# WeatherBoard_v2_0.net
KiCad netlist of a schematic drawn in EAGLE
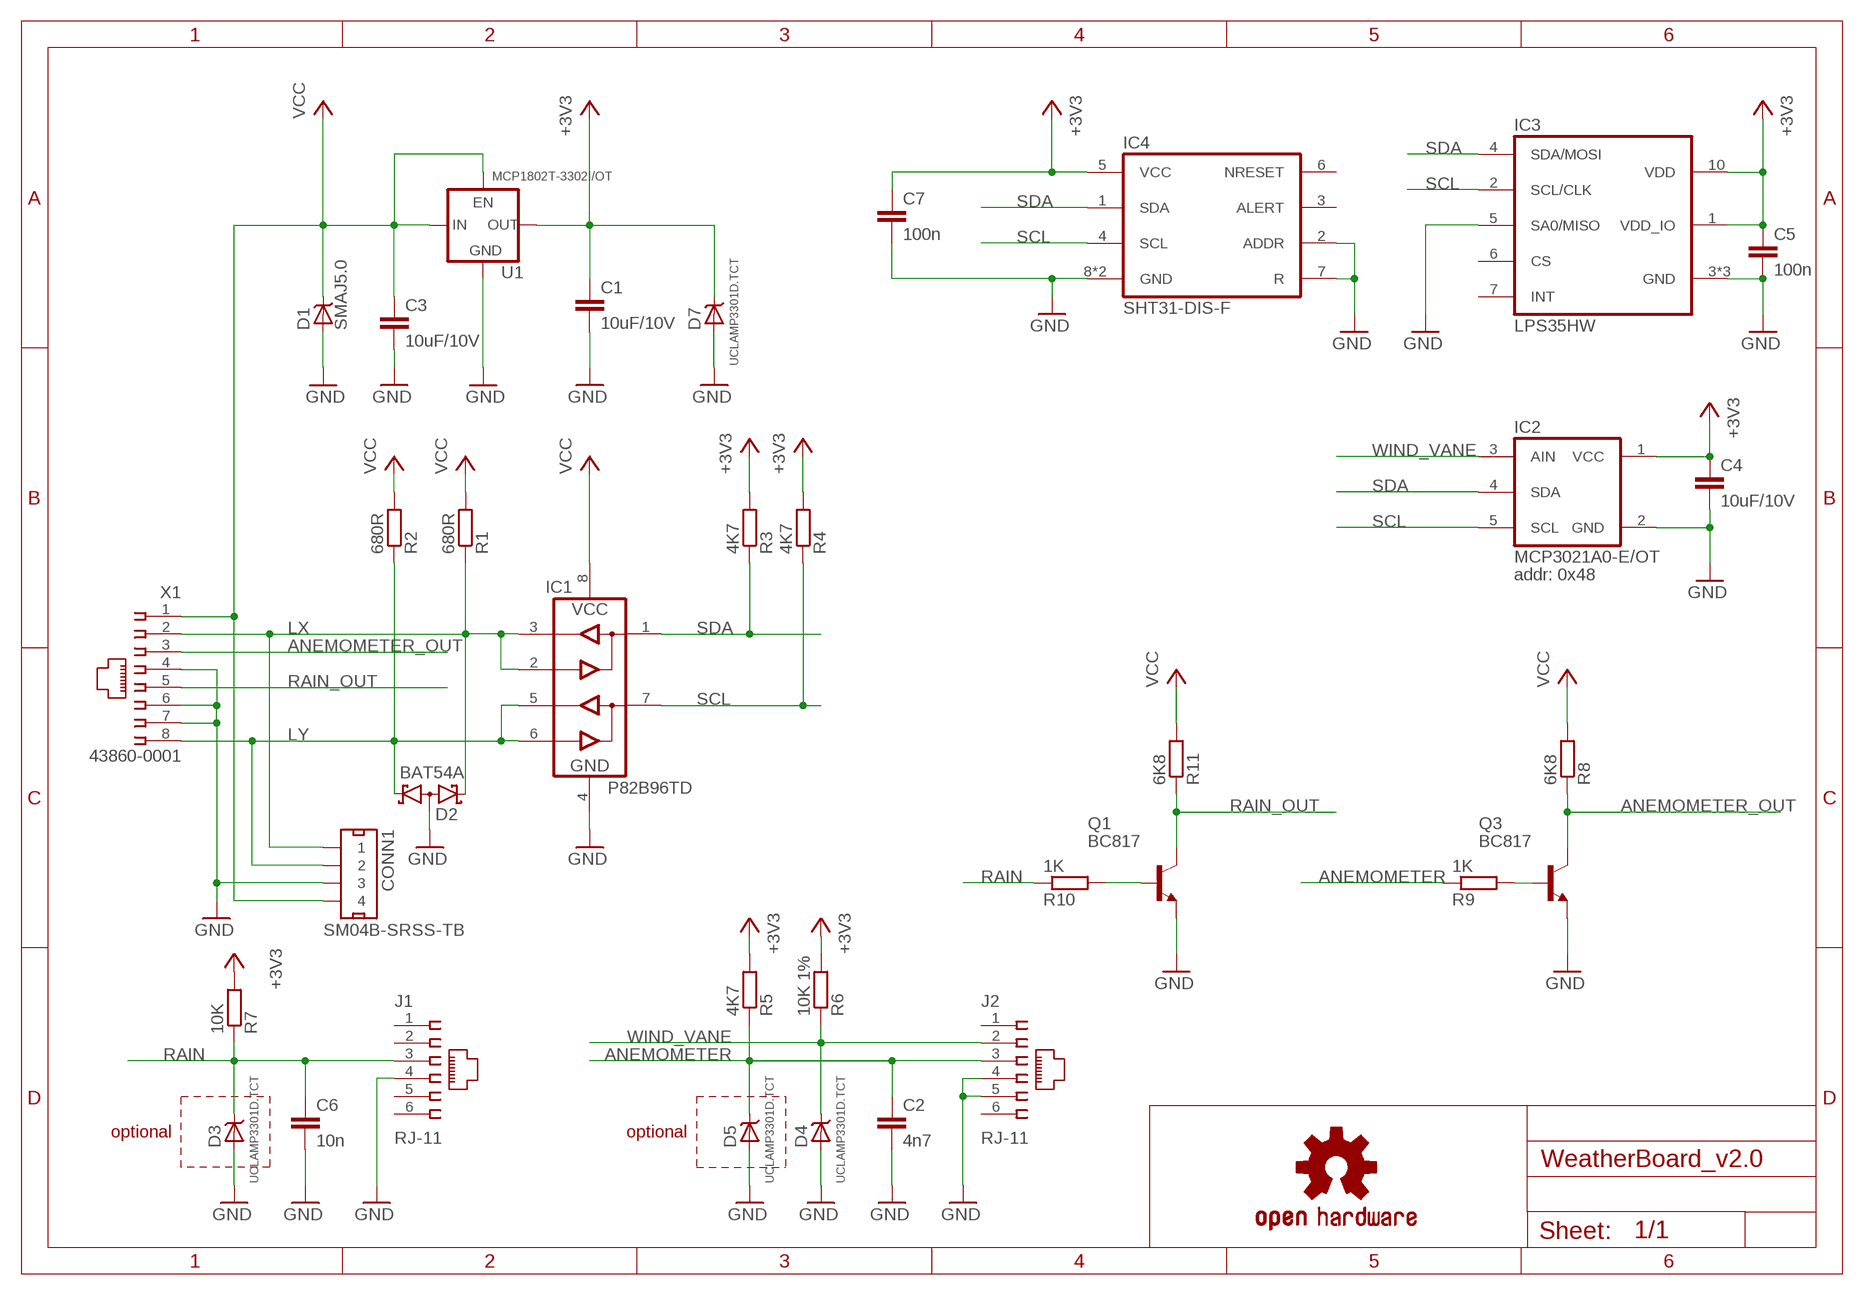
[diagram p0: schematic, sheet 1]

(export (version "E")
  (design (tool "Eeschema 10.0.6"))
  (components
    (comp (ref "C1")
      (value "10uF/10V")
      (footprint "eagle-import:C0805")
      (libsource (lib "eagle-import") (part "C-EUC0805"))
    )
    (comp (ref "C2")
      (value "4n7")
      (footprint "eagle-import:C0805")
      (libsource (lib "eagle-import") (part "C-EUC0805"))
    )
    (comp (ref "C3")
      (value "10uF/10V")
      (footprint "eagle-import:C0805")
      (libsource (lib "eagle-import") (part "C-EUC0805"))
    )
    (comp (ref "C4")
      (value "10uF/10V")
      (footprint "eagle-import:C0805")
      (libsource (lib "eagle-import") (part "C-EUC0805"))
    )
    (comp (ref "C5")
      (value "100n")
      (footprint "eagle-import:C0805")
      (libsource (lib "eagle-import") (part "C-EUC0805"))
    )
    (comp (ref "C6")
      (value "10n")
      (footprint "eagle-import:C0805")
      (libsource (lib "eagle-import") (part "C-EUC0805"))
    )
    (comp (ref "C7")
      (value "100n")
      (footprint "eagle-import:C0805")
      (libsource (lib "eagle-import") (part "C-EUC0805"))
    )
    (comp (ref "CONN1")
      (value "SM04B-SRSS-TB")
      (footprint "eagle-import:JST-SRSS-4-T")
      (libsource (lib "eagle-import") (part "?M04B-SRSS-TBS"))
    )
    (comp (ref "D1")
      (value "SMAJ5.0")
      (footprint "eagle-import:DO214AC")
      (libsource (lib "eagle-import") (part "SM?JA5.0"))
    )
    (comp (ref "D2")
      (value "BAT54A")
      (footprint "eagle-import:SOT23")
      (libsource (lib "eagle-import") (part "BAT54A"))
    )
    (comp (ref "D3")
      (value "UCLAMP3301D.TCT")
      (footprint "eagle-import:SOD323")
      (libsource (lib "eagle-import") (part "UCLAMP3301?.TCTD"))
    )
    (comp (ref "D4")
      (value "UCLAMP3301D.TCT")
      (footprint "eagle-import:SOD323")
      (libsource (lib "eagle-import") (part "UCLAMP3301?.TCTD"))
    )
    (comp (ref "D5")
      (value "UCLAMP3301D.TCT")
      (footprint "eagle-import:SOD323")
      (libsource (lib "eagle-import") (part "UCLAMP3301?.TCTD"))
    )
    (comp (ref "D7")
      (value "UCLAMP3301D.TCT")
      (footprint "eagle-import:SOD323")
      (libsource (lib "eagle-import") (part "UCLAMP3301?.TCTD"))
    )
    (comp (ref "IC1")
      (value "P82B96TD")
      (footprint "eagle-import:SO08")
      (libsource (lib "eagle-import") (part "P82B96?TD"))
    )
    (comp (ref "IC2")
      (value "MCP3021A0-E/OT")
      (footprint "eagle-import:SOT23-5")
      (libsource (lib "eagle-import") (part "MCP3021-E/?OTA0"))
    )
    (comp (ref "IC3")
      (value "LPS35HW")
      (footprint "eagle-import:CCLGA10L")
      (libsource (lib "eagle-import") (part "LPS35HW"))
    )
    (comp (ref "IC4")
      (value "SHT31-DIS-F")
      (footprint "eagle-import:DFN8")
      (libsource (lib "eagle-import") (part "SHT3-DIS1"))
    )
    (comp (ref "J1")
      (value "RJ-11")
      (footprint "eagle-import:615006138421")
      (libsource (lib "eagle-import") (part "RJ-11"))
    )
    (comp (ref "J2")
      (value "RJ-11")
      (footprint "eagle-import:615006138421")
      (libsource (lib "eagle-import") (part "RJ-11"))
    )
    (comp (ref "LOGO1")
      (value "OSHW-LOGOM-COPPER")
      (footprint "eagle-import:OSHW-LOGO-M_COPPER")
      (libsource (lib "eagle-import") (part "OSHW-LOGOM-COPPER"))
    )
    (comp (ref "Q1")
      (value "BC817")
      (footprint "eagle-import:SOT23-BEC")
      (libsource (lib "eagle-import") (part "BC817SMD-40"))
    )
    (comp (ref "Q3")
      (value "BC817")
      (footprint "eagle-import:SOT23-BEC")
      (libsource (lib "eagle-import") (part "BC817SMD-40"))
    )
    (comp (ref "R1")
      (value "680R")
      (footprint "eagle-import:R0805")
      (libsource (lib "eagle-import") (part "R-EU_R0805"))
    )
    (comp (ref "R2")
      (value "680R")
      (footprint "eagle-import:R0805")
      (libsource (lib "eagle-import") (part "R-EU_R0805"))
    )
    (comp (ref "R3")
      (value "4K7")
      (footprint "eagle-import:R0805")
      (libsource (lib "eagle-import") (part "R-EU_R0805"))
    )
    (comp (ref "R4")
      (value "4K7")
      (footprint "eagle-import:R0805")
      (libsource (lib "eagle-import") (part "R-EU_R0805"))
    )
    (comp (ref "R5")
      (value "4K7")
      (footprint "eagle-import:R0805")
      (libsource (lib "eagle-import") (part "R-EU_R0805"))
    )
    (comp (ref "R6")
      (value "10K 1%")
      (footprint "eagle-import:R0805")
      (libsource (lib "eagle-import") (part "R-EU_R0805"))
    )
    (comp (ref "R7")
      (value "10K")
      (footprint "eagle-import:R0805")
      (libsource (lib "eagle-import") (part "R-EU_R0805"))
    )
    (comp (ref "R8")
      (value "6K8")
      (footprint "eagle-import:R0805")
      (libsource (lib "eagle-import") (part "R-EU_R0805"))
    )
    (comp (ref "R9")
      (value "1K")
      (footprint "eagle-import:R0805")
      (libsource (lib "eagle-import") (part "R-EU_R0805"))
    )
    (comp (ref "R10")
      (value "1K")
      (footprint "eagle-import:R0805")
      (libsource (lib "eagle-import") (part "R-EU_R0805"))
    )
    (comp (ref "R11")
      (value "6K8")
      (footprint "eagle-import:R0805")
      (libsource (lib "eagle-import") (part "R-EU_R0805"))
    )
    (comp (ref "U1")
      (value "MCP1802T-3302I/OT")
      (footprint "eagle-import:SOT23-5")
      (libsource (lib "eagle-import") (part "TLV700DD33"))
    )
    (comp (ref "X1")
      (value "43860-0001")
      (footprint "eagle-import:MX-43860-0001")
      (libsource (lib "eagle-import") (part "43860-0001"))
    )
  )
  (nets
    (net (code "1") (name "+3V3") (class "Default")
      (node (ref "C1") (pin "1") (pinfunction "1_1") (pintype "passive"))
      (node (ref "C4") (pin "1") (pinfunction "1_1") (pintype "passive"))
      (node (ref "C5") (pin "1") (pinfunction "1_1") (pintype "passive"))
      (node (ref "C7") (pin "1") (pinfunction "1_1") (pintype "passive"))
      (node (ref "D7") (pin "C") (pinfunction "C_C") (pintype "passive"))
      (node (ref "IC2") (pin "1") (pinfunction "VCC_1") (pintype "power_in"))
      (node (ref "IC3") (pin "1") (pinfunction "VDD_IO_1") (pintype "input"))
      (node (ref "IC3") (pin "10") (pinfunction "VDD_10") (pintype "power_in"))
      (node (ref "IC4") (pin "5") (pinfunction "VCC_5") (pintype "power_in"))
      (node (ref "R3") (pin "2") (pinfunction "2_2") (pintype "passive"))
      (node (ref "R4") (pin "2") (pinfunction "2_2") (pintype "passive"))
      (node (ref "R5") (pin "2") (pinfunction "2_2") (pintype "passive"))
      (node (ref "R6") (pin "2") (pinfunction "2_2") (pintype "passive"))
      (node (ref "R7") (pin "2") (pinfunction "2_2") (pintype "passive"))
      (node (ref "U1") (pin "5") (pinfunction "VOUT_5") (pintype "power_in"))
    )
    (net (code "2") (name "/ANEMOMETER") (class "Default")
      (node (ref "C2") (pin "1") (pinfunction "1_1") (pintype "passive"))
      (node (ref "D5") (pin "C") (pinfunction "C_C") (pintype "passive"))
      (node (ref "J2") (pin "3") (pinfunction "3_3") (pintype "passive"))
      (node (ref "R5") (pin "1") (pinfunction "1_1") (pintype "passive"))
      (node (ref "R9") (pin "1") (pinfunction "1_1") (pintype "passive"))
    )
    (net (code "3") (name "/ANEMOMETER_OUT") (class "Default")
      (node (ref "Q3") (pin "C") (pinfunction "C_C") (pintype "passive"))
      (node (ref "R8") (pin "1") (pinfunction "1_1") (pintype "passive"))
      (node (ref "X1") (pin "3") (pinfunction "3_3") (pintype "passive"))
    )
    (net (code "4") (name "/LX") (class "Default")
      (node (ref "CONN1") (pin "1") (pinfunction "1_1") (pintype "passive"))
      (node (ref "D2") (pin "2") (pinfunction "K2_2") (pintype "passive"))
      (node (ref "IC1") (pin "2") (pinfunction "RX_2") (pintype "open_collector"))
      (node (ref "IC1") (pin "3") (pinfunction "TX_3") (pintype "open_collector"))
      (node (ref "R1") (pin "1") (pinfunction "1_1") (pintype "passive"))
      (node (ref "X1") (pin "2") (pinfunction "2_2") (pintype "passive"))
    )
    (net (code "5") (name "/LY") (class "Default")
      (node (ref "CONN1") (pin "2") (pinfunction "2_2") (pintype "passive"))
      (node (ref "D2") (pin "1") (pinfunction "K1_1") (pintype "passive"))
      (node (ref "IC1") (pin "5") (pinfunction "TY_5") (pintype "open_collector"))
      (node (ref "IC1") (pin "6") (pinfunction "RY_6") (pintype "open_collector"))
      (node (ref "R2") (pin "1") (pinfunction "1_1") (pintype "passive"))
      (node (ref "X1") (pin "8") (pinfunction "8_8") (pintype "passive"))
    )
    (net (code "6") (name "/RAIN") (class "Default")
      (node (ref "C6") (pin "1") (pinfunction "1_1") (pintype "passive"))
      (node (ref "D3") (pin "C") (pinfunction "C_C") (pintype "passive"))
      (node (ref "J1") (pin "3") (pinfunction "3_3") (pintype "passive"))
      (node (ref "R10") (pin "1") (pinfunction "1_1") (pintype "passive"))
      (node (ref "R7") (pin "1") (pinfunction "1_1") (pintype "passive"))
    )
    (net (code "7") (name "/RAIN_OUT") (class "Default")
      (node (ref "Q1") (pin "C") (pinfunction "C_C") (pintype "passive"))
      (node (ref "R11") (pin "1") (pinfunction "1_1") (pintype "passive"))
      (node (ref "X1") (pin "5") (pinfunction "5_5") (pintype "passive"))
    )
    (net (code "8") (name "/SCL") (class "Default")
      (node (ref "IC1") (pin "7") (pinfunction "SY_7") (pintype "input"))
      (node (ref "IC2") (pin "5") (pinfunction "SCL_5") (pintype "input"))
      (node (ref "IC3") (pin "2") (pinfunction "SCL/CLK_2") (pintype "bidirectional"))
      (node (ref "IC4") (pin "4") (pinfunction "SCL_4") (pintype "bidirectional"))
      (node (ref "R4") (pin "1") (pinfunction "1_1") (pintype "passive"))
    )
    (net (code "9") (name "/SDA") (class "Default")
      (node (ref "IC1") (pin "1") (pinfunction "SX_1") (pintype "input"))
      (node (ref "IC2") (pin "4") (pinfunction "SDA_4") (pintype "bidirectional"))
      (node (ref "IC3") (pin "4") (pinfunction "SDA/MOSI_4") (pintype "bidirectional"))
      (node (ref "IC4") (pin "1") (pinfunction "SDA_1") (pintype "bidirectional"))
      (node (ref "R3") (pin "1") (pinfunction "1_1") (pintype "passive"))
    )
    (net (code "10") (name "/WIND_VANE") (class "Default")
      (node (ref "D4") (pin "C") (pinfunction "C_C") (pintype "passive"))
      (node (ref "IC2") (pin "3") (pinfunction "AIN_3") (pintype "bidirectional"))
      (node (ref "J2") (pin "2") (pinfunction "2_2") (pintype "passive"))
      (node (ref "R6") (pin "1") (pinfunction "1_1") (pintype "passive"))
    )
    (net (code "11") (name "GND") (class "Default")
      (node (ref "C1") (pin "2") (pinfunction "2_2") (pintype "passive"))
      (node (ref "C2") (pin "2") (pinfunction "2_2") (pintype "passive"))
      (node (ref "C3") (pin "2") (pinfunction "2_2") (pintype "passive"))
      (node (ref "C4") (pin "2") (pinfunction "2_2") (pintype "passive"))
      (node (ref "C5") (pin "2") (pinfunction "2_2") (pintype "passive"))
      (node (ref "C6") (pin "2") (pinfunction "2_2") (pintype "passive"))
      (node (ref "C7") (pin "2") (pinfunction "2_2") (pintype "passive"))
      (node (ref "CONN1") (pin "3") (pinfunction "3_3") (pintype "passive"))
      (node (ref "D1") (pin "A") (pinfunction "A_A") (pintype "passive"))
      (node (ref "D2") (pin "3") (pinfunction "AA_3") (pintype "passive"))
      (node (ref "D3") (pin "A") (pinfunction "A_A") (pintype "passive"))
      (node (ref "D4") (pin "A") (pinfunction "A_A") (pintype "passive"))
      (node (ref "D5") (pin "A") (pinfunction "A_A") (pintype "passive"))
      (node (ref "D7") (pin "A") (pinfunction "A_A") (pintype "passive"))
      (node (ref "IC1") (pin "4") (pinfunction "GND_4") (pintype "power_in"))
      (node (ref "IC2") (pin "2") (pinfunction "GND_2") (pintype "power_in"))
      (node (ref "IC3") (pin "3") (pinfunction "GND_3") (pintype "power_in"))
      (node (ref "IC3") (pin "5") (pinfunction "SA0/MISO_5") (pintype "bidirectional"))
      (node (ref "IC3") (pin "8") (pinfunction "GND_8") (pintype "power_in"))
      (node (ref "IC3") (pin "9") (pinfunction "GND_9") (pintype "power_in"))
      (node (ref "IC4") (pin "2") (pinfunction "ADDR_2") (pintype "input"))
      (node (ref "IC4") (pin "7") (pinfunction "R_7") (pintype "input"))
      (node (ref "IC4") (pin "8") (pinfunction "GND_8") (pintype "power_in"))
      (node (ref "IC4") (pin "PAD") (pinfunction "GND_PAD") (pintype "power_in"))
      (node (ref "J1") (pin "4") (pinfunction "4_4") (pintype "passive"))
      (node (ref "J2") (pin "4") (pinfunction "4_4") (pintype "passive"))
      (node (ref "J2") (pin "5") (pinfunction "5_5") (pintype "passive"))
      (node (ref "Q1") (pin "E") (pinfunction "E_E") (pintype "passive"))
      (node (ref "Q3") (pin "E") (pinfunction "E_E") (pintype "passive"))
      (node (ref "U1") (pin "2") (pinfunction "GND_2") (pintype "power_in"))
      (node (ref "X1") (pin "4") (pinfunction "4_4") (pintype "passive"))
      (node (ref "X1") (pin "6") (pinfunction "6_6") (pintype "passive"))
      (node (ref "X1") (pin "7") (pinfunction "7_7") (pintype "passive"))
    )
    (net (code "12") (name "Net-(Q1-PadB)") (class "Default")
      (node (ref "Q1") (pin "B") (pinfunction "B_B") (pintype "passive"))
      (node (ref "R10") (pin "2") (pinfunction "2_2") (pintype "passive"))
    )
    (net (code "13") (name "Net-(Q3-PadB)") (class "Default")
      (node (ref "Q3") (pin "B") (pinfunction "B_B") (pintype "passive"))
      (node (ref "R9") (pin "2") (pinfunction "2_2") (pintype "passive"))
    )
    (net (code "14") (name "VCC") (class "Default")
      (node (ref "C3") (pin "1") (pinfunction "1_1") (pintype "passive"))
      (node (ref "CONN1") (pin "4") (pinfunction "4_4") (pintype "passive"))
      (node (ref "D1") (pin "C") (pinfunction "C_C") (pintype "passive"))
      (node (ref "IC1") (pin "8") (pinfunction "VCC_8") (pintype "power_in"))
      (node (ref "R1") (pin "2") (pinfunction "2_2") (pintype "passive"))
      (node (ref "R11") (pin "2") (pinfunction "2_2") (pintype "passive"))
      (node (ref "R2") (pin "2") (pinfunction "2_2") (pintype "passive"))
      (node (ref "R8") (pin "2") (pinfunction "2_2") (pintype "passive"))
      (node (ref "U1") (pin "1") (pinfunction "VIN_1") (pintype "power_in"))
      (node (ref "U1") (pin "3") (pinfunction "EN_3") (pintype "input"))
      (node (ref "X1") (pin "1") (pinfunction "1_1") (pintype "passive"))
    )
    (net (code "15") (name "unconnected-(CONN1-PAD1-PadNC2)") (class "Default")
      (node (ref "CONN1") (pin "NC2") (pinfunction "PAD1_NC2") (pintype "no_connect"))
    )
    (net (code "16") (name "unconnected-(CONN1-PAD2-PadNC1)") (class "Default")
      (node (ref "CONN1") (pin "NC1") (pinfunction "PAD2_NC1") (pintype "no_connect"))
    )
    (net (code "17") (name "unconnected-(IC3-CS-Pad6)") (class "Default")
      (node (ref "IC3") (pin "6") (pinfunction "CS_6") (pintype "input"))
    )
    (net (code "18") (name "unconnected-(IC3-INT-Pad7)") (class "Default")
      (node (ref "IC3") (pin "7") (pinfunction "INT_7") (pintype "output"))
    )
    (net (code "19") (name "unconnected-(IC4-ALERT-Pad3)") (class "Default")
      (node (ref "IC4") (pin "3") (pinfunction "ALERT_3") (pintype "output"))
    )
    (net (code "20") (name "unconnected-(IC4-NRESET-Pad6)") (class "Default")
      (node (ref "IC4") (pin "6") (pinfunction "NRESET_6") (pintype "input"))
    )
    (net (code "21") (name "unconnected-(J1-Pad1)") (class "Default")
      (node (ref "J1") (pin "1") (pinfunction "1_1") (pintype "passive"))
    )
    (net (code "22") (name "unconnected-(J1-Pad2)") (class "Default")
      (node (ref "J1") (pin "2") (pinfunction "2_2") (pintype "passive"))
    )
    (net (code "23") (name "unconnected-(J1-Pad5)") (class "Default")
      (node (ref "J1") (pin "5") (pinfunction "5_5") (pintype "passive"))
    )
    (net (code "24") (name "unconnected-(J1-Pad6)") (class "Default")
      (node (ref "J1") (pin "6") (pinfunction "6_6") (pintype "passive"))
    )
    (net (code "25") (name "unconnected-(J2-Pad1)") (class "Default")
      (node (ref "J2") (pin "1") (pinfunction "1_1") (pintype "passive"))
    )
    (net (code "26") (name "unconnected-(J2-Pad6)") (class "Default")
      (node (ref "J2") (pin "6") (pinfunction "6_6") (pintype "passive"))
    )
  )
)
